# Power.net
KiCad netlist of a schematic drawn in Altium Designer
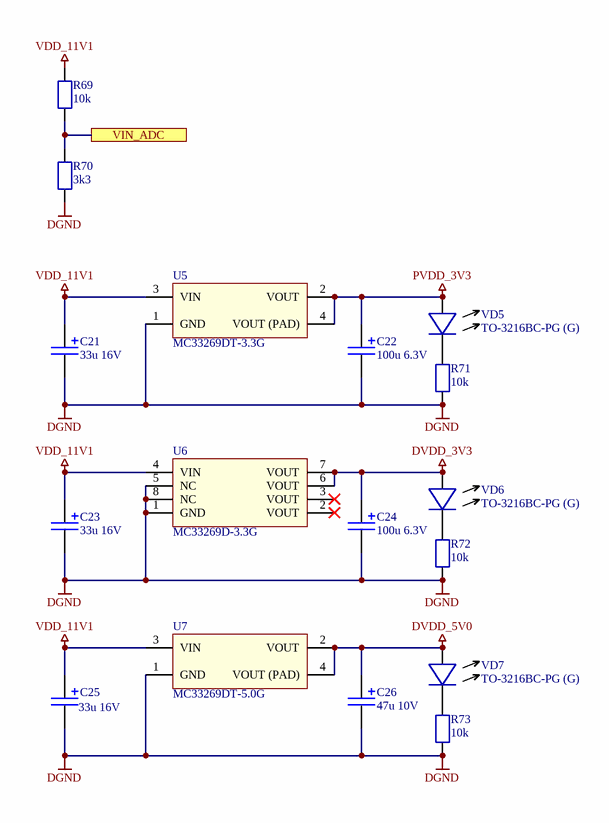
[diagram p0: Power.SchDoc]

(export (version "E")
  (design (tool "Eeschema 10.0.6"))
  (components
    (comp (ref "C21")
      (value "33u 16V")
      (footprint "TECAP_TYPE_B")
      (description "Polarized capacitor")
      (libsource (lib "passive") (part "Capacitor polar"))
    )
    (comp (ref "C22")
      (value "100u 6.3V")
      (footprint "TECAP_TYPE_B")
      (description "Polarized capacitor")
      (libsource (lib "passive") (part "Capacitor polar"))
    )
    (comp (ref "C23")
      (value "33u 16V")
      (footprint "TECAP_TYPE_B")
      (description "Polarized capacitor")
      (libsource (lib "passive") (part "Capacitor polar"))
    )
    (comp (ref "C24")
      (value "100u 6.3V")
      (footprint "TECAP_TYPE_B")
      (description "Polarized capacitor")
      (libsource (lib "passive") (part "Capacitor polar"))
    )
    (comp (ref "C25")
      (value "33u 16V")
      (footprint "TECAP_TYPE_B")
      (description "Polarized capacitor")
      (libsource (lib "passive") (part "Capacitor polar"))
    )
    (comp (ref "C26")
      (value "47u 10V")
      (footprint "TECAP_TYPE_B")
      (description "Polarized capacitor")
      (libsource (lib "passive") (part "Capacitor polar"))
    )
    (comp (ref "R69")
      (value "10k")
      (footprint "R_0603/1608")
      (description "Resistor")
      (libsource (lib "passive") (part "Resistor"))
    )
    (comp (ref "R70")
      (value "3k3")
      (footprint "R_0603/1608")
      (description "Resistor")
      (libsource (lib "passive") (part "Resistor"))
    )
    (comp (ref "R71")
      (value "10k")
      (footprint "R_0603/1608")
      (description "Resistor")
      (libsource (lib "passive") (part "Resistor"))
    )
    (comp (ref "R72")
      (value "10k")
      (footprint "R_0603/1608")
      (description "Resistor")
      (libsource (lib "passive") (part "Resistor"))
    )
    (comp (ref "R73")
      (value "10k")
      (footprint "R_0603/1608")
      (description "Resistor")
      (libsource (lib "passive") (part "Resistor"))
    )
    (comp (ref "U5")
      (value "MC33269DT-3.3G")
      (footprint "TO252AA/DPAK")
      (description "LDO voltage regulator")
      (libsource (lib "power") (part "MC33269DT"))
    )
    (comp (ref "U6")
      (value "MC33269D-3.3G")
      (footprint "SO8_1.27")
      (description "LDO voltage regulator")
      (libsource (lib "power") (part "MC33269D"))
    )
    (comp (ref "U7")
      (value "MC33269DT-5.0G")
      (footprint "TO252AA/DPAK")
      (description "LDO voltage regulator")
      (libsource (lib "power") (part "MC33269DT"))
    )
    (comp (ref "VD5")
      (value "TO-3216BC-PG (G)")
      (footprint "LED_0603/1608")
      (description "LED")
      (libsource (lib "indication") (part "LED"))
    )
    (comp (ref "VD6")
      (value "TO-3216BC-PG (G)")
      (footprint "LED_0603/1608")
      (description "LED")
      (libsource (lib "indication") (part "LED"))
    )
    (comp (ref "VD7")
      (value "TO-3216BC-PG (G)")
      (footprint "LED_0603/1608")
      (description "LED")
      (libsource (lib "indication") (part "LED"))
    )
  )
  (nets
    (net (code "1") (name "/VIN_ADC") (class "Default")
      (node (ref "R69") (pin "1") (pintype "passive"))
      (node (ref "R70") (pin "2") (pintype "passive"))
    )
    (net (code "2") (name "DGND") (class "Default")
      (node (ref "C21") (pin "2") (pinfunction "NEG_2") (pintype "passive"))
      (node (ref "C22") (pin "2") (pinfunction "NEG_2") (pintype "passive"))
      (node (ref "C23") (pin "2") (pinfunction "NEG_2") (pintype "passive"))
      (node (ref "C24") (pin "2") (pinfunction "NEG_2") (pintype "passive"))
      (node (ref "C25") (pin "2") (pinfunction "NEG_2") (pintype "passive"))
      (node (ref "C26") (pin "2") (pinfunction "NEG_2") (pintype "passive"))
      (node (ref "R70") (pin "1") (pintype "passive"))
      (node (ref "R71") (pin "1") (pintype "passive"))
      (node (ref "R72") (pin "1") (pintype "passive"))
      (node (ref "R73") (pin "1") (pintype "passive"))
      (node (ref "U5") (pin "1") (pinfunction "GND_1") (pintype "power_in"))
      (node (ref "U6") (pin "1") (pinfunction "GND_1") (pintype "power_in"))
      (node (ref "U6") (pin "5") (pinfunction "NC_5") (pintype "power_in"))
      (node (ref "U6") (pin "8") (pinfunction "NC_8") (pintype "power_in"))
      (node (ref "U7") (pin "1") (pinfunction "GND_1") (pintype "power_in"))
    )
    (net (code "3") (name "DVDD_3V3") (class "Default")
      (node (ref "C24") (pin "1") (pinfunction "POS_1") (pintype "passive"))
      (node (ref "U6") (pin "6") (pinfunction "VOUT_6") (pintype "power_in"))
      (node (ref "U6") (pin "7") (pinfunction "VOUT_7") (pintype "power_in"))
      (node (ref "VD6") (pin "A") (pinfunction "A_A") (pintype "passive"))
    )
    (net (code "4") (name "DVDD_5V0") (class "Default")
      (node (ref "C26") (pin "1") (pinfunction "POS_1") (pintype "passive"))
      (node (ref "U7") (pin "2") (pinfunction "VOUT_2") (pintype "power_in"))
      (node (ref "U7") (pin "4") (pinfunction "VOUT_(PAD)_4") (pintype "power_in"))
      (node (ref "VD7") (pin "A") (pinfunction "A_A") (pintype "passive"))
    )
    (net (code "5") (name "Net-(R71-Pad2)") (class "Default")
      (node (ref "R71") (pin "2") (pintype "passive"))
      (node (ref "VD5") (pin "C") (pinfunction "C_C") (pintype "passive"))
    )
    (net (code "6") (name "Net-(R72-Pad2)") (class "Default")
      (node (ref "R72") (pin "2") (pintype "passive"))
      (node (ref "VD6") (pin "C") (pinfunction "C_C") (pintype "passive"))
    )
    (net (code "7") (name "Net-(R73-Pad2)") (class "Default")
      (node (ref "R73") (pin "2") (pintype "passive"))
      (node (ref "VD7") (pin "C") (pinfunction "C_C") (pintype "passive"))
    )
    (net (code "8") (name "PVDD_3V3") (class "Default")
      (node (ref "C22") (pin "1") (pinfunction "POS_1") (pintype "passive"))
      (node (ref "U5") (pin "2") (pinfunction "VOUT_2") (pintype "power_in"))
      (node (ref "U5") (pin "4") (pinfunction "VOUT_(PAD)_4") (pintype "power_in"))
      (node (ref "VD5") (pin "A") (pinfunction "A_A") (pintype "passive"))
    )
    (net (code "9") (name "VDD_11V1") (class "Default")
      (node (ref "C21") (pin "1") (pinfunction "POS_1") (pintype "passive"))
      (node (ref "C23") (pin "1") (pinfunction "POS_1") (pintype "passive"))
      (node (ref "C25") (pin "1") (pinfunction "POS_1") (pintype "passive"))
      (node (ref "R69") (pin "2") (pintype "passive"))
      (node (ref "U5") (pin "3") (pinfunction "VIN_3") (pintype "power_in"))
      (node (ref "U6") (pin "4") (pinfunction "VIN_4") (pintype "power_in"))
      (node (ref "U7") (pin "3") (pinfunction "VIN_3") (pintype "power_in"))
    )
    (net (code "10") (name "unconnected-(U6-VOUT-Pad2)") (class "Default")
      (node (ref "U6") (pin "2") (pinfunction "VOUT_2") (pintype "power_in+no_connect"))
    )
    (net (code "11") (name "unconnected-(U6-VOUT-Pad3)") (class "Default")
      (node (ref "U6") (pin "3") (pinfunction "VOUT_3") (pintype "power_in+no_connect"))
    )
  )
)
